# MPU-Control.net
KiCad netlist of a schematic drawn in Altium Designer
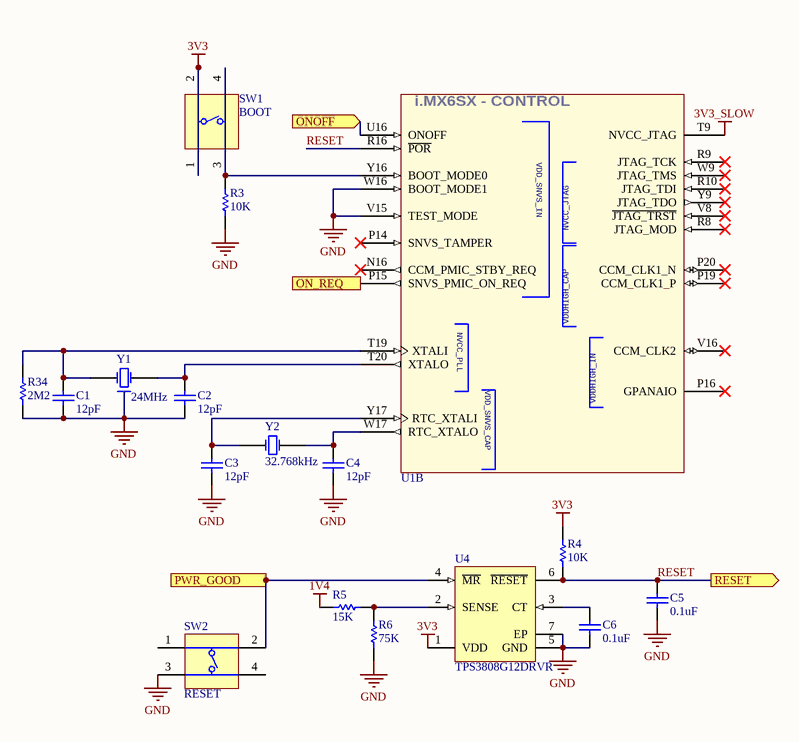
[diagram p0: MPU-Control.SchDoc]

(export (version "E")
  (design (tool "Eeschema 10.0.6"))
  (components
    (comp (ref "C1")
      (value "12pF")
      (footprint "C0402[1005X55]")
      (description "12pF 50V 5% 0402 (1005 Metric)")
      (fields (field (name "PARTNUMBER") "GRM1555C1H120JA01D") (field (name "MANUFACTURER") "Murata"))
      (libsource (lib "Capacitors") (part "CAP_12pF_50V_0402_5%"))
    )
    (comp (ref "C2")
      (value "12pF")
      (footprint "C0402[1005X55]")
      (description "12pF 50V 5% 0402 (1005 Metric)")
      (fields (field (name "PARTNUMBER") "GRM1555C1H120JA01D") (field (name "MANUFACTURER") "Murata"))
      (libsource (lib "Capacitors") (part "CAP_12pF_50V_0402_5%"))
    )
    (comp (ref "C3")
      (value "12pF")
      (footprint "C0402[1005X55]")
      (description "12pF 50V 5% 0402 (1005 Metric)")
      (fields (field (name "PARTNUMBER") "GRM1555C1H120JA01D") (field (name "MANUFACTURER") "Murata"))
      (libsource (lib "Capacitors") (part "CAP_12pF_50V_0402_5%"))
    )
    (comp (ref "C4")
      (value "12pF")
      (footprint "C0402[1005X55]")
      (description "12pF 50V 5% 0402 (1005 Metric)")
      (fields (field (name "PARTNUMBER") "GRM1555C1H120JA01D") (field (name "MANUFACTURER") "Murata"))
      (libsource (lib "Capacitors") (part "CAP_12pF_50V_0402_5%"))
    )
    (comp (ref "C5")
      (value "0.1uF")
      (footprint "C0402[1005X55]")
      (description "0.1uF 6.3V 10% 0402 (1005 Metric)")
      (fields (field (name "PARTNUMBER") "GRM155R70J104KA01D") (field (name "MANUFACTURER") "Murata"))
      (libsource (lib "Capacitors") (part "CAP_0.1uF_6.3V_0402_10%"))
    )
    (comp (ref "C6")
      (value "0.1uF")
      (footprint "C0402[1005X55]")
      (description "0.1uF 100V 10% 0402 (1005 Metric)")
      (fields (field (name "PARTNUMBER") "GRM155R62A104KE14D") (field (name "MANUFACTURER") "Murata"))
      (libsource (lib "Capacitors") (part "CAP_0.1uF_100V_0402_10%"))
    )
    (comp (ref "R3")
      (value "10K")
      (footprint "R0402[1005]")
      (description "10K 0.063W 1% 0402 (1005 Metric)")
      (fields (field (name "MANUFACTURER") "KOA Speer") (field (name "PARTNUMBER") "RK73H1ETTP1002F"))
      (libsource (lib "Resistors") (part "RES_10K_0402_1%"))
    )
    (comp (ref "R4")
      (value "10K")
      (footprint "R0402[1005]")
      (description "10K 0.063W 1% 0402 (1005 Metric)")
      (fields (field (name "MANUFACTURER") "KOA Speer") (field (name "PARTNUMBER") "RK73H1ETTP1002F"))
      (libsource (lib "Resistors") (part "RES_10K_0402_1%"))
    )
    (comp (ref "R5")
      (value "15K")
      (footprint "R0402[1005]")
      (description "15K 0.063W 1% 0402 (1005 Metric)")
      (fields (field (name "MANUFACTURER") "KOA Speer") (field (name "PARTNUMBER") "RK73H1ETTP1502F"))
      (libsource (lib "Resistors") (part "RES_15K_0402_1%"))
    )
    (comp (ref "R6")
      (value "75K")
      (footprint "R0402[1005]")
      (description "75K 0.063W 1% 0402 (1005 Metric)")
      (fields (field (name "MANUFACTURER") "KOA Speer") (field (name "PARTNUMBER") "RK73H1ETTP7502F"))
      (libsource (lib "Resistors") (part "RES_75K_0402_1%"))
    )
    (comp (ref "R34")
      (value "2M2")
      (footprint "R0402[1005]")
      (description "2M2 0.063W 1% 0402 (1005 Metric)")
      (fields (field (name "MANUFACTURER") "KOA Speer") (field (name "PARTNUMBER") "RK73H1ETTP2204F"))
      (libsource (lib "Resistors") (part "RES_2M2_0402_1%"))
    )
    (comp (ref "SW1")
      (value "BOOT")
      (footprint "SWITCH")
      (description "Switch, SPNO Push Button SMD")
      (fields
        (field (name "MANUFACTURER") "C&K Components")
        (field (name "PARTNUMBER") "PTS810 SJM 250 SMTR LFS")
      )
      (libsource (lib "Components") (part "DIPT-DTSM-6"))
    )
    (comp (ref "SW2")
      (value "RESET")
      (footprint "SWITCH")
      (description "Switch, SPNO Push Button SMD")
      (fields
        (field (name "MANUFACTURER") "C&K Components")
        (field (name "PARTNUMBER") "PTS810 SJM 250 SMTR LFS")
      )
      (libsource (lib "") (part "DIPT-DTSM-6_1"))
    )
    (comp (ref "U1")
      (value "MCIMX6X3EVO10AB")
      (footprint "BGA-400")
      (description "IC MPU I.MX6SX 1GHZ 400MAPBGA")
      (fields (field (name "MANUFACTURER") "NXP"))
      (libsource (lib "ICs") (part "MCIMX6X3EVO10AB"))
    )
    (comp (ref "U4")
      (value "TPS3808G12DRVR")
      (footprint "WSON-6")
      (fields (field (name "MANUFACTURER") "Texas Instruments"))
      (libsource (lib "ICs") (part "TPS3808G12DRVR"))
    )
    (comp (ref "Y1")
      (value "24MHz")
      (footprint "CRYSTAL_2.0x1.6")
      (fields (field (name "PARTNUMBER") "FA-128 24.0000MF10Z-W3") (field (name "MANUFACTURER") "EPSON"))
      (libsource (lib "Components") (part "FA-128 24.0000MF10Z-W3"))
    )
    (comp (ref "Y2")
      (value "32.768kHz")
      (footprint "CRYSTAL_2.0x1.2")
      (fields (field (name "PARTNUMBER") "ABS06-32.768KHZ-9-1-T") (field (name "MANUFACTURER") "Abracon"))
      (libsource (lib "Components") (part "ABS06-32.768KHZ-9-1-T"))
    )
  )
  (nets
    (net (code "1") (name "/ONOFF") (class "Default")
      (node (ref "U1") (pin "U16") (pinfunction "ONOFF_U16") (pintype "input"))
    )
    (net (code "2") (name "/ON_REQ") (class "Default")
      (node (ref "U1") (pin "P15") (pinfunction "SNVS_PMIC_ON_REQ_P15") (pintype "output"))
    )
    (net (code "3") (name "/PWR_GOOD") (class "Default")
      (node (ref "SW2") (pin "2") (pinfunction "T2_2") (pintype "passive"))
      (node (ref "U4") (pin "4") (pinfunction "~{MR}_4") (pintype "input"))
    )
    (net (code "4") (name "/RESET") (class "Default")
      (node (ref "C5") (pin "2") (pinfunction "2_2") (pintype "passive"))
      (node (ref "R4") (pin "1") (pinfunction "1_1") (pintype "passive"))
      (node (ref "U1") (pin "R16") (pinfunction "~{POR}_R16") (pintype "input"))
      (node (ref "U4") (pin "6") (pinfunction "~{RESET}_6") (pintype "tri_state"))
    )
    (net (code "5") (name "1V4") (class "Default")
      (node (ref "R5") (pin "2") (pinfunction "2_2") (pintype "passive"))
    )
    (net (code "6") (name "3V3") (class "Default")
      (node (ref "R4") (pin "2") (pinfunction "2_2") (pintype "passive"))
      (node (ref "SW1") (pin "1") (pinfunction "T1_1") (pintype "passive"))
      (node (ref "SW1") (pin "2") (pinfunction "T2_2") (pintype "passive"))
      (node (ref "U4") (pin "1") (pinfunction "VDD_1") (pintype "power_in"))
    )
    (net (code "7") (name "3V3_SLOW") (class "Default")
      (node (ref "U1") (pin "T9") (pinfunction "NVCC_JTAG_T9") (pintype "power_in"))
    )
    (net (code "8") (name "GND") (class "Default")
      (node (ref "C1") (pin "1") (pinfunction "1_1") (pintype "passive"))
      (node (ref "C2") (pin "1") (pinfunction "1_1") (pintype "passive"))
      (node (ref "C3") (pin "1") (pinfunction "1_1") (pintype "passive"))
      (node (ref "C4") (pin "1") (pinfunction "1_1") (pintype "passive"))
      (node (ref "C5") (pin "1") (pinfunction "1_1") (pintype "passive"))
      (node (ref "C6") (pin "1") (pinfunction "1_1") (pintype "passive"))
      (node (ref "R3") (pin "1") (pinfunction "1_1") (pintype "passive"))
      (node (ref "R34") (pin "1") (pinfunction "1_1") (pintype "passive"))
      (node (ref "R6") (pin "1") (pinfunction "1_1") (pintype "passive"))
      (node (ref "SW2") (pin "3") (pinfunction "T3_3") (pintype "passive"))
      (node (ref "U1") (pin "V15") (pinfunction "TEST_MODE_V15") (pintype "input"))
      (node (ref "U1") (pin "W16") (pinfunction "BOOT_MODE1_W16") (pintype "input"))
      (node (ref "U4") (pin "5") (pinfunction "GND_5") (pintype "power_in"))
      (node (ref "U4") (pin "7") (pinfunction "EP_7") (pintype "power_in"))
      (node (ref "Y1") (pin "2") (pinfunction "2_2") (pintype "passive"))
    )
    (net (code "9") (name "Net-(U1B-BOOT_MODE0)") (class "Default")
      (node (ref "R3") (pin "2") (pinfunction "2_2") (pintype "passive"))
      (node (ref "SW1") (pin "3") (pinfunction "T3_3") (pintype "passive"))
      (node (ref "SW1") (pin "4") (pinfunction "T3_4") (pintype "passive"))
      (node (ref "U1") (pin "Y16") (pinfunction "BOOT_MODE0_Y16") (pintype "input"))
    )
    (net (code "10") (name "Net-(U1B-RTC_XTALI)") (class "Default")
      (node (ref "C3") (pin "2") (pinfunction "2_2") (pintype "passive"))
      (node (ref "U1") (pin "Y17") (pinfunction "RTC_XTALI_Y17") (pintype "input"))
      (node (ref "Y2") (pin "1") (pinfunction "X1_1") (pintype "passive"))
    )
    (net (code "11") (name "Net-(U1B-RTC_XTALO)") (class "Default")
      (node (ref "C4") (pin "2") (pinfunction "2_2") (pintype "passive"))
      (node (ref "U1") (pin "W17") (pinfunction "RTC_XTALO_W17") (pintype "output"))
      (node (ref "Y2") (pin "2") (pinfunction "X2_2") (pintype "passive"))
    )
    (net (code "12") (name "Net-(U1B-XTALI)") (class "Default")
      (node (ref "C1") (pin "2") (pinfunction "2_2") (pintype "passive"))
      (node (ref "R34") (pin "2") (pinfunction "2_2") (pintype "passive"))
      (node (ref "U1") (pin "T19") (pinfunction "XTALI_T19") (pintype "input"))
      (node (ref "Y1") (pin "1") (pinfunction "X1_1") (pintype "passive"))
    )
    (net (code "13") (name "Net-(U1B-XTALO)") (class "Default")
      (node (ref "C2") (pin "2") (pinfunction "2_2") (pintype "passive"))
      (node (ref "U1") (pin "T20") (pinfunction "XTALO_T20") (pintype "output"))
      (node (ref "Y1") (pin "3") (pinfunction "X2_3") (pintype "passive"))
    )
    (net (code "14") (name "Net-(U4-CT)") (class "Default")
      (node (ref "C6") (pin "2") (pinfunction "2_2") (pintype "passive"))
      (node (ref "U4") (pin "3") (pinfunction "CT_3") (pintype "input"))
    )
    (net (code "15") (name "Net-(U4-SENSE)") (class "Default")
      (node (ref "R5") (pin "1") (pinfunction "1_1") (pintype "passive"))
      (node (ref "R6") (pin "2") (pinfunction "2_2") (pintype "passive"))
      (node (ref "U4") (pin "2") (pinfunction "SENSE_2") (pintype "input"))
    )
    (net (code "16") (name "unconnected-(SW2-T1-Pad1)") (class "Default")
      (node (ref "SW2") (pin "1") (pinfunction "T1_1") (pintype "passive"))
    )
    (net (code "17") (name "unconnected-(SW2-T3-Pad4)") (class "Default")
      (node (ref "SW2") (pin "4") (pinfunction "T3_4") (pintype "passive"))
    )
    (net (code "18") (name "unconnected-(U1B-CCM_CLK1_N-PadP20)") (class "Default")
      (node (ref "U1") (pin "P20") (pinfunction "CCM_CLK1_N_P20") (pintype "bidirectional+no_connect"))
    )
    (net (code "19") (name "unconnected-(U1B-CCM_CLK1_P-PadP19)") (class "Default")
      (node (ref "U1") (pin "P19") (pinfunction "CCM_CLK1_P_P19") (pintype "bidirectional+no_connect"))
    )
    (net (code "20") (name "unconnected-(U1B-CCM_CLK2-PadV16)") (class "Default")
      (node (ref "U1") (pin "V16") (pinfunction "CCM_CLK2_V16") (pintype "bidirectional+no_connect"))
    )
    (net (code "21") (name "unconnected-(U1B-CCM_PMIC_STBY_REQ-PadN16)") (class "Default")
      (node (ref "U1") (pin "N16") (pinfunction "CCM_PMIC_STBY_REQ_N16") (pintype "output+no_connect"))
    )
    (net (code "22") (name "unconnected-(U1B-GPANAIO-PadP16)") (class "Default")
      (node (ref "U1") (pin "P16") (pinfunction "GPANAIO_P16") (pintype "power_in+no_connect"))
    )
    (net (code "23") (name "unconnected-(U1B-JTAG_MOD-PadR8)") (class "Default")
      (node (ref "U1") (pin "R8") (pinfunction "JTAG_MOD_R8") (pintype "input+no_connect"))
    )
    (net (code "24") (name "unconnected-(U1B-JTAG_TCK-PadR9)") (class "Default")
      (node (ref "U1") (pin "R9") (pinfunction "JTAG_TCK_R9") (pintype "input+no_connect"))
    )
    (net (code "25") (name "unconnected-(U1B-JTAG_TDI-PadR10)") (class "Default")
      (node (ref "U1") (pin "R10") (pinfunction "JTAG_TDI_R10") (pintype "input+no_connect"))
    )
    (net (code "26") (name "unconnected-(U1B-JTAG_TDO-PadY9)") (class "Default")
      (node (ref "U1") (pin "Y9") (pinfunction "JTAG_TDO_Y9") (pintype "output+no_connect"))
    )
    (net (code "27") (name "unconnected-(U1B-JTAG_TMS-PadW9)") (class "Default")
      (node (ref "U1") (pin "W9") (pinfunction "JTAG_TMS_W9") (pintype "input+no_connect"))
    )
    (net (code "28") (name "unconnected-(U1B-SNVS_TAMPER-PadP14)") (class "Default")
      (node (ref "U1") (pin "P14") (pinfunction "SNVS_TAMPER_P14") (pintype "input+no_connect"))
    )
    (net (code "29") (name "unconnected-(U1B-~{JTAG_TRST}-PadV8)") (class "Default")
      (node (ref "U1") (pin "V8") (pinfunction "~{JTAG_TRST}_V8") (pintype "input+no_connect"))
    )
  )
)
